# Udi_s_Bridge_brake.net
KiCad netlist of a schematic drawn in EAGLE
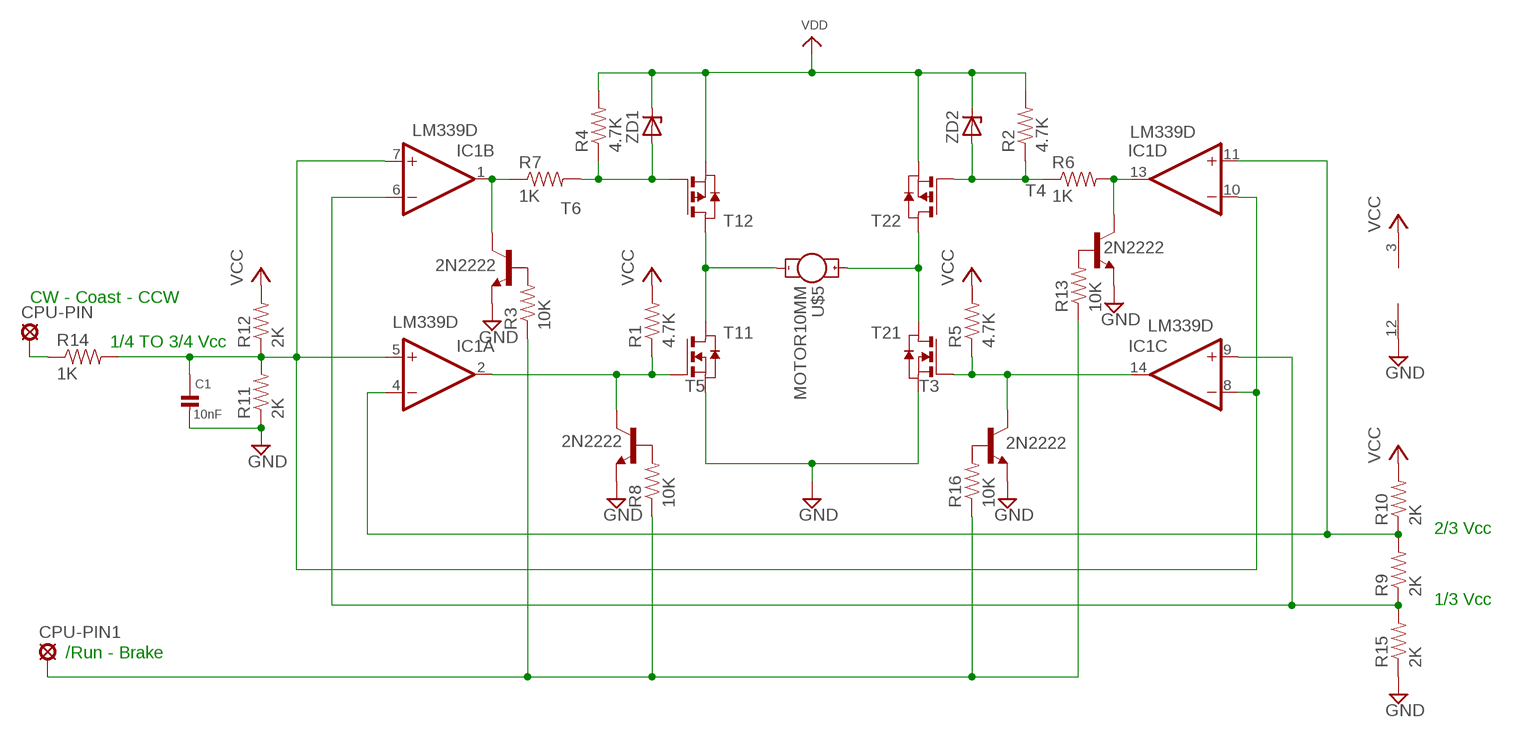
[diagram p0: schematic, sheet 1]

(export (version "E")
  (design (tool "Eeschema 10.0.6"))
  (components
    (comp (ref "C1")
      (value "10nF")
      (footprint "eagle-import:0805")
      (libsource (lib "eagle-import") (part "CAP_CERAMIC0805"))
    )
    (comp (ref "CPU-PIN")
      (value "CPU I/O pin")
      (footprint "eagle-import:LSP13")
      (libsource (lib "eagle-import") (part "LSP13"))
    )
    (comp (ref "CPU-PIN1")
      (value "CPU I/O pin")
      (footprint "eagle-import:LSP13")
      (libsource (lib "eagle-import") (part "LSP13"))
    )
    (comp (ref "IC1")
      (value "LM339D")
      (footprint "eagle-import:SO14")
      (libsource (lib "eagle-import") (part "LM339D"))
    )
    (comp (ref "R1")
      (value "4.7K")
      (footprint "eagle-import:0805")
      (libsource (lib "eagle-import") (part "RESISTOR0805-RES"))
    )
    (comp (ref "R2")
      (value "4.7K")
      (footprint "eagle-import:0805")
      (libsource (lib "eagle-import") (part "RESISTOR0805-RES"))
    )
    (comp (ref "R3")
      (value "10K")
      (footprint "eagle-import:0805")
      (libsource (lib "eagle-import") (part "RESISTOR0805-RES"))
    )
    (comp (ref "R4")
      (value "4.7K")
      (footprint "eagle-import:0805")
      (libsource (lib "eagle-import") (part "RESISTOR0805-RES"))
    )
    (comp (ref "R5")
      (value "4.7K")
      (footprint "eagle-import:0805")
      (libsource (lib "eagle-import") (part "RESISTOR0805-RES"))
    )
    (comp (ref "R6")
      (value "1K")
      (footprint "eagle-import:0805")
      (libsource (lib "eagle-import") (part "RESISTOR0805-RES"))
    )
    (comp (ref "R7")
      (value "1K")
      (footprint "eagle-import:0805")
      (libsource (lib "eagle-import") (part "RESISTOR0805-RES"))
    )
    (comp (ref "R8")
      (value "10K")
      (footprint "eagle-import:0805")
      (libsource (lib "eagle-import") (part "RESISTOR0805-RES"))
    )
    (comp (ref "R9")
      (value "2K")
      (footprint "eagle-import:0805")
      (libsource (lib "eagle-import") (part "RESISTOR0805-RES"))
    )
    (comp (ref "R10")
      (value "2K")
      (footprint "eagle-import:0805")
      (libsource (lib "eagle-import") (part "RESISTOR0805-RES"))
    )
    (comp (ref "R11")
      (value "2K")
      (footprint "eagle-import:0805")
      (libsource (lib "eagle-import") (part "RESISTOR0805-RES"))
    )
    (comp (ref "R12")
      (value "2K")
      (footprint "eagle-import:0805")
      (libsource (lib "eagle-import") (part "RESISTOR0805-RES"))
    )
    (comp (ref "R13")
      (value "10K")
      (footprint "eagle-import:0805")
      (libsource (lib "eagle-import") (part "RESISTOR0805-RES"))
    )
    (comp (ref "R14")
      (value "1K")
      (footprint "eagle-import:0805")
      (libsource (lib "eagle-import") (part "RESISTOR0805-RES"))
    )
    (comp (ref "R15")
      (value "2K")
      (footprint "eagle-import:0805")
      (libsource (lib "eagle-import") (part "RESISTOR0805-RES"))
    )
    (comp (ref "R16")
      (value "10K")
      (footprint "eagle-import:0805")
      (libsource (lib "eagle-import") (part "RESISTOR0805-RES"))
    )
    (comp (ref "T1")
      (value "PN_MOSFET-SO8")
      (footprint "eagle-import:SO8")
      (libsource (lib "eagle-import") (part "PN_MOSFET-SO8"))
    )
    (comp (ref "T2")
      (value "PN_MOSFET-SO8")
      (footprint "eagle-import:SO8")
      (libsource (lib "eagle-import") (part "PN_MOSFET-SO8"))
    )
    (comp (ref "T3")
      (value "2N2222")
      (footprint "eagle-import:TO18")
      (libsource (lib "eagle-import") (part "2N2222"))
    )
    (comp (ref "T4")
      (value "2N2222")
      (footprint "eagle-import:TO18")
      (libsource (lib "eagle-import") (part "2N2222"))
    )
    (comp (ref "T5")
      (value "2N2222")
      (footprint "eagle-import:TO18")
      (libsource (lib "eagle-import") (part "2N2222"))
    )
    (comp (ref "T6")
      (value "2N2222")
      (footprint "eagle-import:TO18")
      (libsource (lib "eagle-import") (part "2N2222"))
    )
    (comp (ref "U$5")
      (value "MOTOR10MM")
      (footprint "eagle-import:VIBE-MOTOR-10MM")
      (libsource (lib "eagle-import") (part "MOTOR10MM"))
    )
    (comp (ref "ZD1")
      (value "ZENERSOD-123")
      (footprint "eagle-import:SOD-123")
      (libsource (lib "eagle-import") (part "ZENERSOD-123"))
    )
    (comp (ref "ZD2")
      (value "ZENERSOD-123")
      (footprint "eagle-import:SOD-123")
      (libsource (lib "eagle-import") (part "ZENERSOD-123"))
    )
  )
  (nets
    (net (code "1") (name "GND") (class "Default")
      (node (ref "C1") (pin "2") (pinfunction "P$2_2") (pintype "passive"))
      (node (ref "IC1") (pin "12") (pinfunction "GND_12") (pintype "power_in"))
      (node (ref "R11") (pin "1") (pinfunction "1_1") (pintype "passive"))
      (node (ref "R15") (pin "1") (pinfunction "1_1") (pintype "passive"))
      (node (ref "T1") (pin "1") (pinfunction "S_1") (pintype "passive"))
      (node (ref "T2") (pin "1") (pinfunction "S_1") (pintype "passive"))
      (node (ref "T3") (pin "1") (pinfunction "E_1") (pintype "passive"))
      (node (ref "T4") (pin "1") (pinfunction "E_1") (pintype "passive"))
      (node (ref "T5") (pin "1") (pinfunction "E_1") (pintype "passive"))
      (node (ref "T6") (pin "1") (pinfunction "E_1") (pintype "passive"))
    )
    (net (code "2") (name "Net-(C1-P$1)") (class "Default")
      (node (ref "C1") (pin "1") (pinfunction "P$1_1") (pintype "passive"))
      (node (ref "IC1") (pin "10") (pinfunction "-IN_10") (pintype "input"))
      (node (ref "IC1") (pin "5") (pinfunction "+IN_5") (pintype "input"))
      (node (ref "IC1") (pin "7") (pinfunction "+IN_7") (pintype "input"))
      (node (ref "IC1") (pin "8") (pinfunction "-IN_8") (pintype "input"))
      (node (ref "R11") (pin "2") (pinfunction "2_2") (pintype "passive"))
      (node (ref "R12") (pin "1") (pinfunction "1_1") (pintype "passive"))
      (node (ref "R14") (pin "2") (pinfunction "2_2") (pintype "passive"))
    )
    (net (code "3") (name "Net-(CPU-PIN-PadMP)") (class "Default")
      (node (ref "CPU-PIN") (pin "MP") (pinfunction "MP_MP") (pintype "passive"))
      (node (ref "R14") (pin "1") (pinfunction "1_1") (pintype "passive"))
    )
    (net (code "4") (name "Net-(CPU-PIN1-PadMP)") (class "Default")
      (node (ref "CPU-PIN1") (pin "MP") (pinfunction "MP_MP") (pintype "passive"))
      (node (ref "R13") (pin "1") (pinfunction "1_1") (pintype "passive"))
      (node (ref "R16") (pin "1") (pinfunction "1_1") (pintype "passive"))
      (node (ref "R3") (pin "1") (pinfunction "1_1") (pintype "passive"))
      (node (ref "R8") (pin "1") (pinfunction "1_1") (pintype "passive"))
    )
    (net (code "5") (name "Net-(IC1A--IN)") (class "Default")
      (node (ref "IC1") (pin "11") (pinfunction "+IN_11") (pintype "input"))
      (node (ref "IC1") (pin "4") (pinfunction "-IN_4") (pintype "input"))
      (node (ref "R10") (pin "1") (pinfunction "1_1") (pintype "passive"))
      (node (ref "R9") (pin "2") (pinfunction "2_2") (pintype "passive"))
    )
    (net (code "6") (name "Net-(IC1A-OUT)") (class "Default")
      (node (ref "IC1") (pin "2") (pinfunction "OUT_2") (pintype "open_collector"))
      (node (ref "R1") (pin "1") (pinfunction "1_1") (pintype "passive"))
      (node (ref "T1") (pin "2") (pinfunction "G_2") (pintype "passive"))
      (node (ref "T5") (pin "3") (pinfunction "C_3") (pintype "passive"))
    )
    (net (code "7") (name "Net-(IC1B--IN)") (class "Default")
      (node (ref "IC1") (pin "6") (pinfunction "-IN_6") (pintype "input"))
      (node (ref "IC1") (pin "9") (pinfunction "+IN_9") (pintype "input"))
      (node (ref "R15") (pin "2") (pinfunction "2_2") (pintype "passive"))
      (node (ref "R9") (pin "1") (pinfunction "1_1") (pintype "passive"))
    )
    (net (code "8") (name "Net-(IC1B-OUT)") (class "Default")
      (node (ref "IC1") (pin "1") (pinfunction "OUT_1") (pintype "open_collector"))
      (node (ref "R7") (pin "1") (pinfunction "1_1") (pintype "passive"))
      (node (ref "T6") (pin "3") (pinfunction "C_3") (pintype "passive"))
    )
    (net (code "9") (name "Net-(IC1C-OUT)") (class "Default")
      (node (ref "IC1") (pin "14") (pinfunction "OUT_14") (pintype "open_collector"))
      (node (ref "R5") (pin "1") (pinfunction "1_1") (pintype "passive"))
      (node (ref "T2") (pin "2") (pinfunction "G_2") (pintype "passive"))
      (node (ref "T3") (pin "3") (pinfunction "C_3") (pintype "passive"))
    )
    (net (code "10") (name "Net-(IC1D-OUT)") (class "Default")
      (node (ref "IC1") (pin "13") (pinfunction "OUT_13") (pintype "open_collector"))
      (node (ref "R6") (pin "2") (pinfunction "2_2") (pintype "passive"))
      (node (ref "T4") (pin "3") (pinfunction "C_3") (pintype "passive"))
    )
    (net (code "11") (name "Net-(T1A-D-Pad7)") (class "Default")
      (node (ref "T1") (pin "5") (pinfunction "D_5") (pintype "passive"))
      (node (ref "T1") (pin "6") (pinfunction "D_6") (pintype "passive"))
      (node (ref "T1") (pin "7") (pinfunction "D_7") (pintype "passive"))
      (node (ref "T1") (pin "8") (pinfunction "D_8") (pintype "passive"))
      (node (ref "U$5") (pin "-") (pinfunction "-_-") (pintype "bidirectional"))
    )
    (net (code "12") (name "Net-(T1B-G)") (class "Default")
      (node (ref "R4") (pin "1") (pinfunction "1_1") (pintype "passive"))
      (node (ref "R7") (pin "2") (pinfunction "2_2") (pintype "passive"))
      (node (ref "T1") (pin "4") (pinfunction "G_4") (pintype "passive"))
      (node (ref "ZD1") (pin "A") (pinfunction "A_A") (pintype "passive"))
    )
    (net (code "13") (name "Net-(T2A-D-Pad7)") (class "Default")
      (node (ref "T2") (pin "5") (pinfunction "D_5") (pintype "passive"))
      (node (ref "T2") (pin "6") (pinfunction "D_6") (pintype "passive"))
      (node (ref "T2") (pin "7") (pinfunction "D_7") (pintype "passive"))
      (node (ref "T2") (pin "8") (pinfunction "D_8") (pintype "passive"))
      (node (ref "U$5") (pin "+") (pinfunction "+_+") (pintype "bidirectional"))
    )
    (net (code "14") (name "Net-(T2B-G)") (class "Default")
      (node (ref "R2") (pin "1") (pinfunction "1_1") (pintype "passive"))
      (node (ref "R6") (pin "1") (pinfunction "1_1") (pintype "passive"))
      (node (ref "T2") (pin "4") (pinfunction "G_4") (pintype "passive"))
      (node (ref "ZD2") (pin "A") (pinfunction "A_A") (pintype "passive"))
    )
    (net (code "15") (name "Net-(T3-B)") (class "Default")
      (node (ref "R16") (pin "2") (pinfunction "2_2") (pintype "passive"))
      (node (ref "T3") (pin "2") (pinfunction "B_2") (pintype "passive"))
    )
    (net (code "16") (name "Net-(T4-B)") (class "Default")
      (node (ref "R13") (pin "2") (pinfunction "2_2") (pintype "passive"))
      (node (ref "T4") (pin "2") (pinfunction "B_2") (pintype "passive"))
    )
    (net (code "17") (name "Net-(T5-B)") (class "Default")
      (node (ref "R8") (pin "2") (pinfunction "2_2") (pintype "passive"))
      (node (ref "T5") (pin "2") (pinfunction "B_2") (pintype "passive"))
    )
    (net (code "18") (name "Net-(T6-B)") (class "Default")
      (node (ref "R3") (pin "2") (pinfunction "2_2") (pintype "passive"))
      (node (ref "T6") (pin "2") (pinfunction "B_2") (pintype "passive"))
    )
    (net (code "19") (name "VCC") (class "Default")
      (node (ref "IC1") (pin "3") (pinfunction "V+_3") (pintype "power_in"))
      (node (ref "R1") (pin "2") (pinfunction "2_2") (pintype "passive"))
      (node (ref "R10") (pin "2") (pinfunction "2_2") (pintype "passive"))
      (node (ref "R12") (pin "2") (pinfunction "2_2") (pintype "passive"))
      (node (ref "R5") (pin "2") (pinfunction "2_2") (pintype "passive"))
    )
    (net (code "20") (name "VDD") (class "Default")
      (node (ref "R2") (pin "2") (pinfunction "2_2") (pintype "passive"))
      (node (ref "R4") (pin "2") (pinfunction "2_2") (pintype "passive"))
      (node (ref "T1") (pin "3") (pinfunction "S_3") (pintype "passive"))
      (node (ref "T2") (pin "3") (pinfunction "S_3") (pintype "passive"))
      (node (ref "ZD1") (pin "C") (pinfunction "C_C") (pintype "passive"))
      (node (ref "ZD2") (pin "C") (pinfunction "C_C") (pintype "passive"))
    )
  )
)
